# ballistic-supply.net
KiCad netlist of a schematic drawn in EAGLE
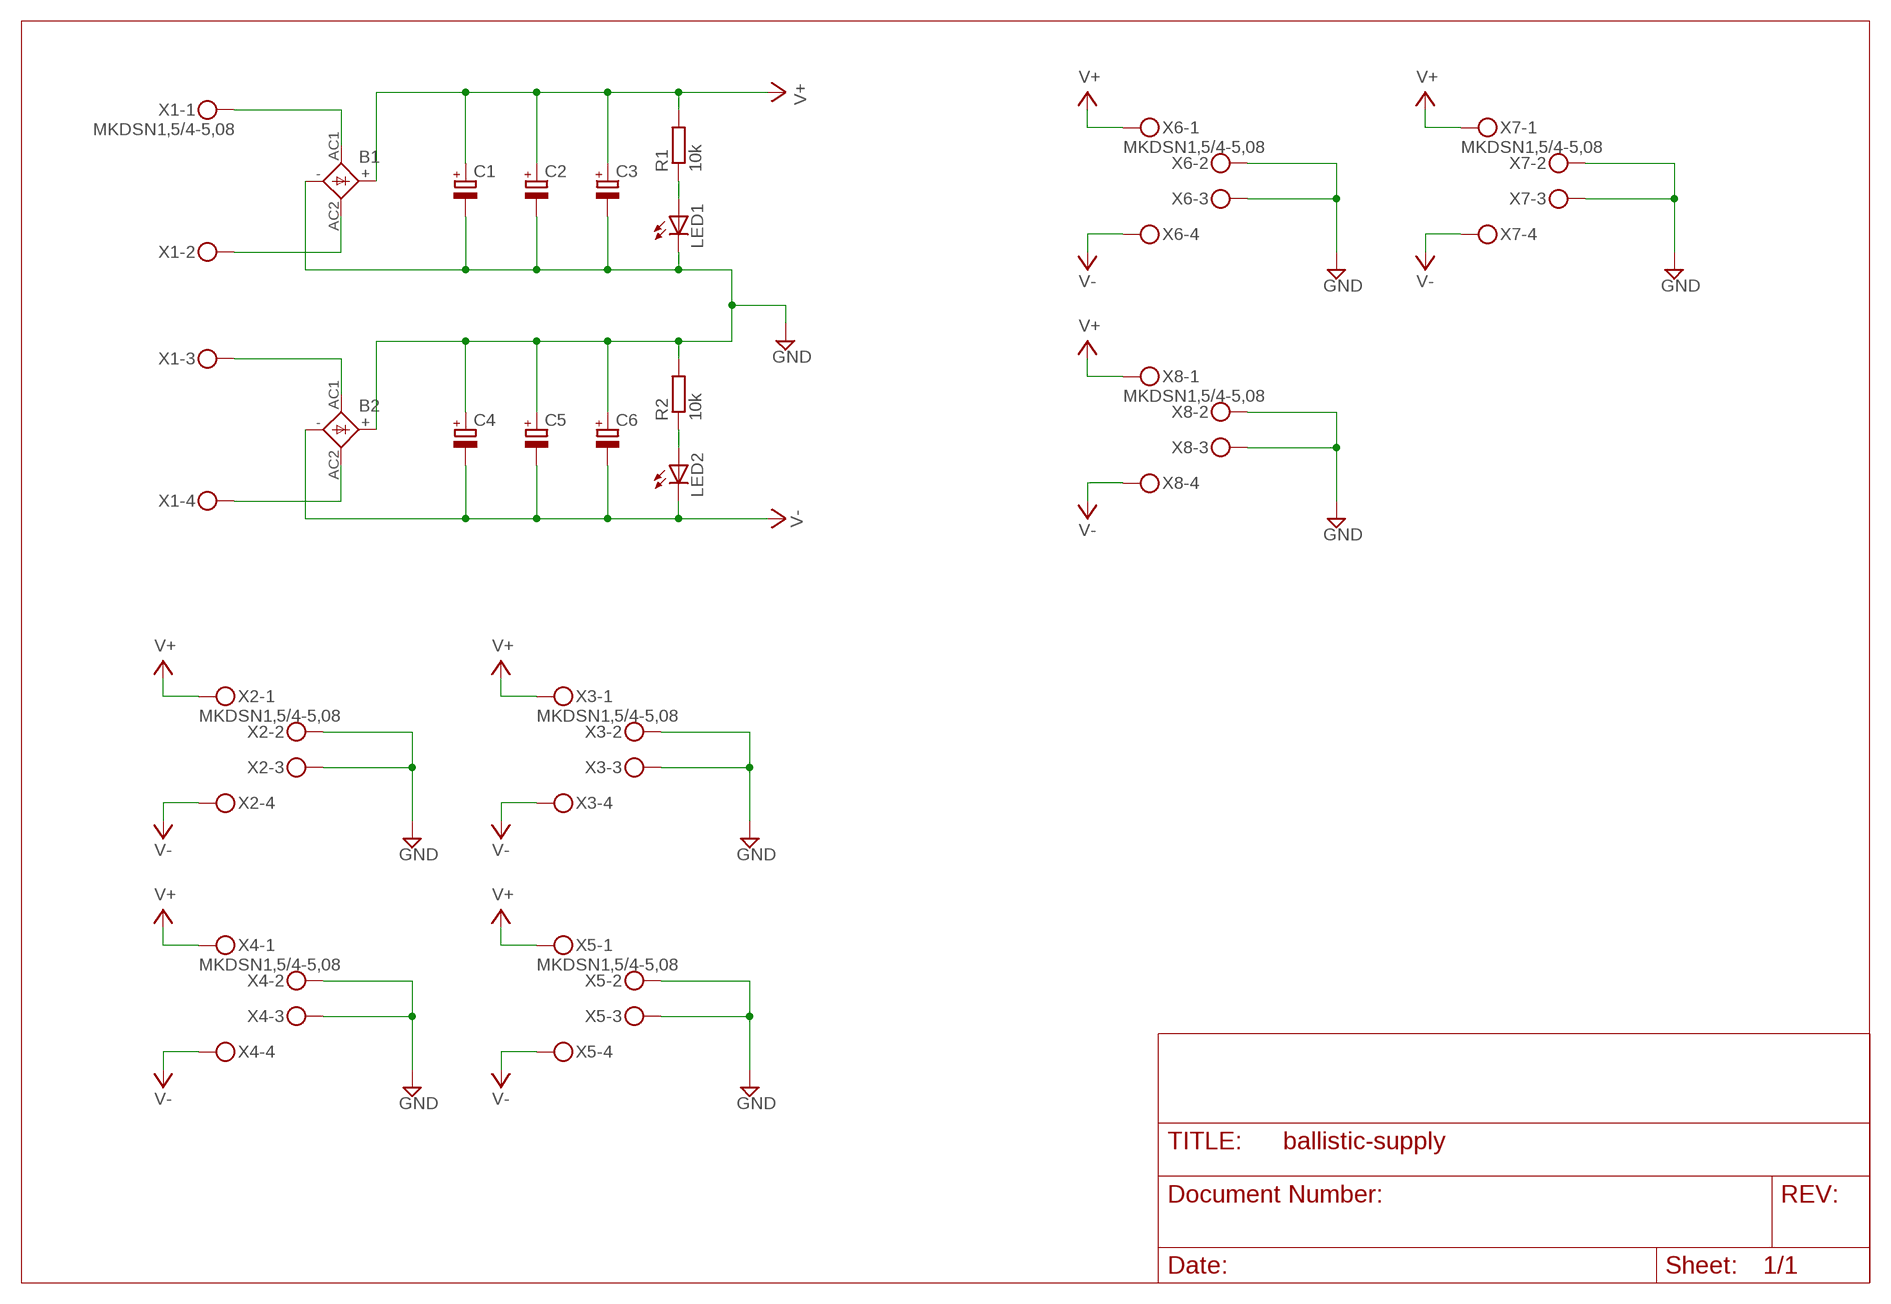
[diagram p0: schematic, sheet 1]

(export (version "E")
  (design (tool "Eeschema 10.0.6"))
  (components
    (comp (ref "B1")
      (value "SKB32")
      (footprint "eagle-import:SKB32")
      (libsource (lib "eagle-import") (part "SKB32"))
    )
    (comp (ref "B2")
      (value "SKB32")
      (footprint "eagle-import:SKB32")
      (libsource (lib "eagle-import") (part "SKB32"))
    )
    (comp (ref "C1")
      (value "CPOL-EUE7.5-18")
      (footprint "eagle-import:E7,5-18")
      (libsource (lib "eagle-import") (part "CPOL-EUE7.5-18"))
    )
    (comp (ref "C2")
      (value "CPOL-EUE7.5-18")
      (footprint "eagle-import:E7,5-18")
      (libsource (lib "eagle-import") (part "CPOL-EUE7.5-18"))
    )
    (comp (ref "C3")
      (value "CPOL-EUE7.5-18")
      (footprint "eagle-import:E7,5-18")
      (libsource (lib "eagle-import") (part "CPOL-EUE7.5-18"))
    )
    (comp (ref "C4")
      (value "CPOL-EUE7.5-18")
      (footprint "eagle-import:E7,5-18")
      (libsource (lib "eagle-import") (part "CPOL-EUE7.5-18"))
    )
    (comp (ref "C5")
      (value "CPOL-EUE7.5-18")
      (footprint "eagle-import:E7,5-18")
      (libsource (lib "eagle-import") (part "CPOL-EUE7.5-18"))
    )
    (comp (ref "C6")
      (value "CPOL-EUE7.5-18")
      (footprint "eagle-import:E7,5-18")
      (libsource (lib "eagle-import") (part "CPOL-EUE7.5-18"))
    )
    (comp (ref "LED1")
      (value "LEDSMT1206")
      (footprint "eagle-import:1206")
      (libsource (lib "eagle-import") (part "LEDSMT1206"))
    )
    (comp (ref "LED2")
      (value "LEDSMT1206")
      (footprint "eagle-import:1206")
      (libsource (lib "eagle-import") (part "LEDSMT1206"))
    )
    (comp (ref "R1")
      (value "10k")
      (footprint "eagle-import:M1206")
      (libsource (lib "eagle-import") (part "R-EU_M1206"))
    )
    (comp (ref "R2")
      (value "10k")
      (footprint "eagle-import:M1206")
      (libsource (lib "eagle-import") (part "R-EU_M1206"))
    )
    (comp (ref "X1")
      (value "MKDSN1,5/4-5,08")
      (footprint "eagle-import:MKDSN1,5_4-5,08")
      (libsource (lib "eagle-import") (part "MKDSN1,5/4-5,08"))
    )
    (comp (ref "X2")
      (value "MKDSN1,5/4-5,08")
      (footprint "eagle-import:MKDSN1,5_4-5,08")
      (libsource (lib "eagle-import") (part "MKDSN1,5/4-5,08"))
    )
    (comp (ref "X3")
      (value "MKDSN1,5/4-5,08")
      (footprint "eagle-import:MKDSN1,5_4-5,08")
      (libsource (lib "eagle-import") (part "MKDSN1,5/4-5,08"))
    )
    (comp (ref "X4")
      (value "MKDSN1,5/4-5,08")
      (footprint "eagle-import:MKDSN1,5_4-5,08")
      (libsource (lib "eagle-import") (part "MKDSN1,5/4-5,08"))
    )
    (comp (ref "X5")
      (value "MKDSN1,5/4-5,08")
      (footprint "eagle-import:MKDSN1,5_4-5,08")
      (libsource (lib "eagle-import") (part "MKDSN1,5/4-5,08"))
    )
    (comp (ref "X6")
      (value "MKDSN1,5/4-5,08")
      (footprint "eagle-import:MKDSN1,5_4-5,08")
      (libsource (lib "eagle-import") (part "MKDSN1,5/4-5,08"))
    )
    (comp (ref "X7")
      (value "MKDSN1,5/4-5,08")
      (footprint "eagle-import:MKDSN1,5_4-5,08")
      (libsource (lib "eagle-import") (part "MKDSN1,5/4-5,08"))
    )
    (comp (ref "X8")
      (value "MKDSN1,5/4-5,08")
      (footprint "eagle-import:MKDSN1,5_4-5,08")
      (libsource (lib "eagle-import") (part "MKDSN1,5/4-5,08"))
    )
  )
  (nets
    (net (code "1") (name "GND") (class "Default")
      (node (ref "B1") (pin "-") (pinfunction "-_-") (pintype "passive"))
      (node (ref "B2") (pin "+") (pinfunction "+_+") (pintype "passive"))
      (node (ref "C1") (pin "-") (pinfunction "-_-") (pintype "passive"))
      (node (ref "C2") (pin "-") (pinfunction "-_-") (pintype "passive"))
      (node (ref "C3") (pin "-") (pinfunction "-_-") (pintype "passive"))
      (node (ref "C4") (pin "+") (pinfunction "+_+") (pintype "passive"))
      (node (ref "C5") (pin "+") (pinfunction "+_+") (pintype "passive"))
      (node (ref "C6") (pin "+") (pinfunction "+_+") (pintype "passive"))
      (node (ref "LED1") (pin "C") (pinfunction "C_C") (pintype "passive"))
      (node (ref "R2") (pin "2") (pinfunction "2_2") (pintype "passive"))
      (node (ref "X2") (pin "2") (pinfunction "KL_2") (pintype "passive"))
      (node (ref "X2") (pin "3") (pinfunction "KL_3") (pintype "passive"))
      (node (ref "X3") (pin "2") (pinfunction "KL_2") (pintype "passive"))
      (node (ref "X3") (pin "3") (pinfunction "KL_3") (pintype "passive"))
      (node (ref "X4") (pin "2") (pinfunction "KL_2") (pintype "passive"))
      (node (ref "X4") (pin "3") (pinfunction "KL_3") (pintype "passive"))
      (node (ref "X5") (pin "2") (pinfunction "KL_2") (pintype "passive"))
      (node (ref "X5") (pin "3") (pinfunction "KL_3") (pintype "passive"))
      (node (ref "X6") (pin "2") (pinfunction "KL_2") (pintype "passive"))
      (node (ref "X6") (pin "3") (pinfunction "KL_3") (pintype "passive"))
      (node (ref "X7") (pin "2") (pinfunction "KL_2") (pintype "passive"))
      (node (ref "X7") (pin "3") (pinfunction "KL_3") (pintype "passive"))
      (node (ref "X8") (pin "2") (pinfunction "KL_2") (pintype "passive"))
      (node (ref "X8") (pin "3") (pinfunction "KL_3") (pintype "passive"))
    )
    (net (code "2") (name "Net-(LED1-PadA)") (class "Default")
      (node (ref "LED1") (pin "A") (pinfunction "A_A") (pintype "passive"))
      (node (ref "R1") (pin "1") (pinfunction "1_1") (pintype "passive"))
    )
    (net (code "3") (name "Net-(LED2-PadA)") (class "Default")
      (node (ref "LED2") (pin "A") (pinfunction "A_A") (pintype "passive"))
      (node (ref "R2") (pin "1") (pinfunction "1_1") (pintype "passive"))
    )
    (net (code "4") (name "Net-(X1A-KL)") (class "Default")
      (node (ref "B1") (pin "AC1") (pinfunction "AC1_AC1") (pintype "passive"))
      (node (ref "X1") (pin "1") (pinfunction "KL_1") (pintype "passive"))
    )
    (net (code "5") (name "Net-(X1B-KL)") (class "Default")
      (node (ref "B1") (pin "AC2") (pinfunction "AC2_AC2") (pintype "passive"))
      (node (ref "X1") (pin "2") (pinfunction "KL_2") (pintype "passive"))
    )
    (net (code "6") (name "Net-(X1C-KL)") (class "Default")
      (node (ref "B2") (pin "AC1") (pinfunction "AC1_AC1") (pintype "passive"))
      (node (ref "X1") (pin "3") (pinfunction "KL_3") (pintype "passive"))
    )
    (net (code "7") (name "Net-(X1D-KL)") (class "Default")
      (node (ref "B2") (pin "AC2") (pinfunction "AC2_AC2") (pintype "passive"))
      (node (ref "X1") (pin "4") (pinfunction "KL_4") (pintype "passive"))
    )
    (net (code "8") (name "V+") (class "Default")
      (node (ref "B1") (pin "+") (pinfunction "+_+") (pintype "passive"))
      (node (ref "C1") (pin "+") (pinfunction "+_+") (pintype "passive"))
      (node (ref "C2") (pin "+") (pinfunction "+_+") (pintype "passive"))
      (node (ref "C3") (pin "+") (pinfunction "+_+") (pintype "passive"))
      (node (ref "R1") (pin "2") (pinfunction "2_2") (pintype "passive"))
      (node (ref "X2") (pin "1") (pinfunction "KL_1") (pintype "passive"))
      (node (ref "X3") (pin "1") (pinfunction "KL_1") (pintype "passive"))
      (node (ref "X4") (pin "1") (pinfunction "KL_1") (pintype "passive"))
      (node (ref "X5") (pin "1") (pinfunction "KL_1") (pintype "passive"))
      (node (ref "X6") (pin "1") (pinfunction "KL_1") (pintype "passive"))
      (node (ref "X7") (pin "1") (pinfunction "KL_1") (pintype "passive"))
      (node (ref "X8") (pin "1") (pinfunction "KL_1") (pintype "passive"))
    )
    (net (code "9") (name "V-") (class "Default")
      (node (ref "B2") (pin "-") (pinfunction "-_-") (pintype "passive"))
      (node (ref "C4") (pin "-") (pinfunction "-_-") (pintype "passive"))
      (node (ref "C5") (pin "-") (pinfunction "-_-") (pintype "passive"))
      (node (ref "C6") (pin "-") (pinfunction "-_-") (pintype "passive"))
      (node (ref "LED2") (pin "C") (pinfunction "C_C") (pintype "passive"))
      (node (ref "X2") (pin "4") (pinfunction "KL_4") (pintype "passive"))
      (node (ref "X3") (pin "4") (pinfunction "KL_4") (pintype "passive"))
      (node (ref "X4") (pin "4") (pinfunction "KL_4") (pintype "passive"))
      (node (ref "X5") (pin "4") (pinfunction "KL_4") (pintype "passive"))
      (node (ref "X6") (pin "4") (pinfunction "KL_4") (pintype "passive"))
      (node (ref "X7") (pin "4") (pinfunction "KL_4") (pintype "passive"))
      (node (ref "X8") (pin "4") (pinfunction "KL_4") (pintype "passive"))
    )
  )
)
